# usbcan_20190426.net
KiCad netlist of a schematic drawn in EAGLE
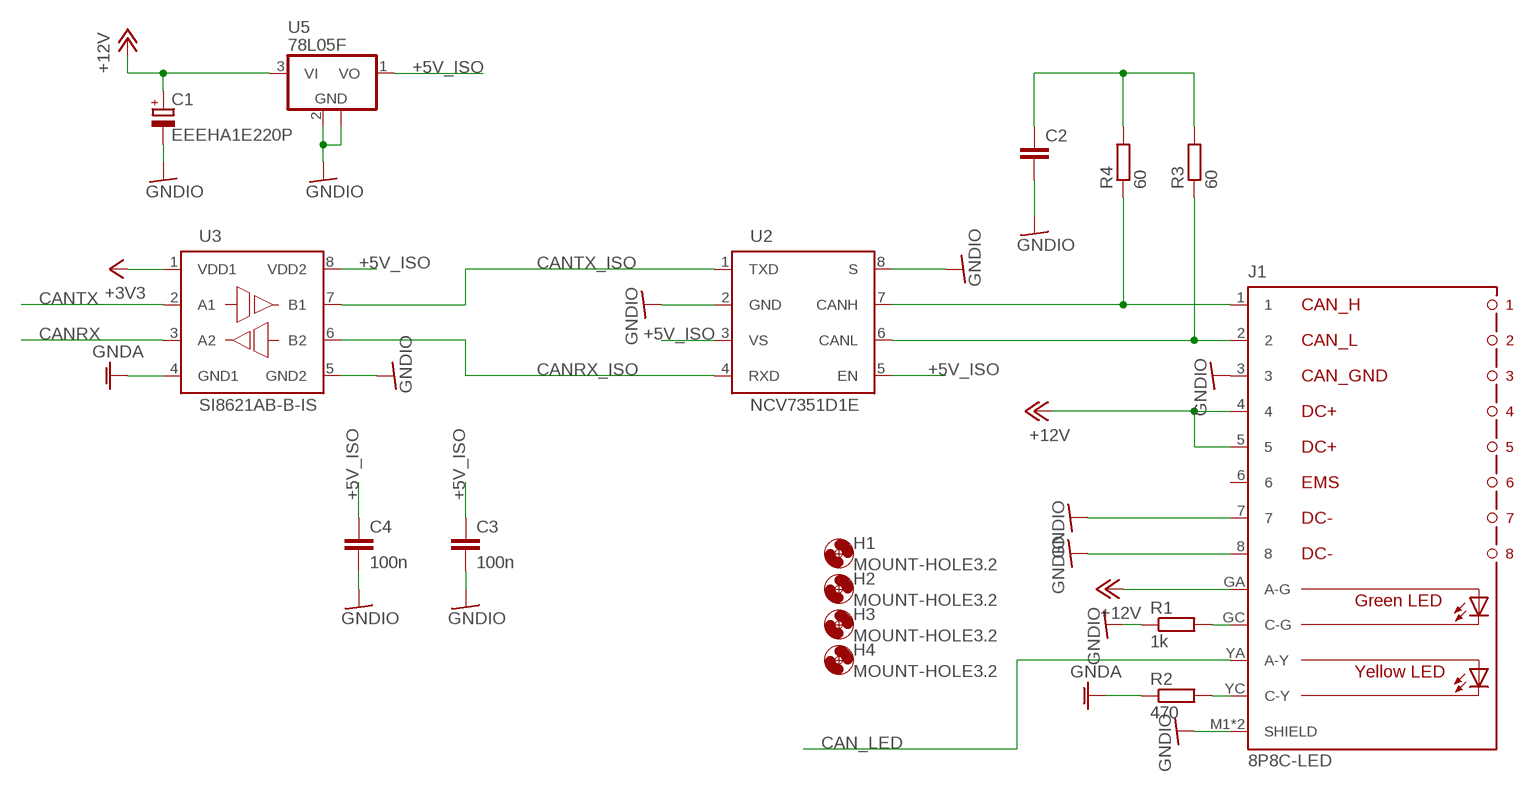
[diagram p0: schematic, sheet 1]
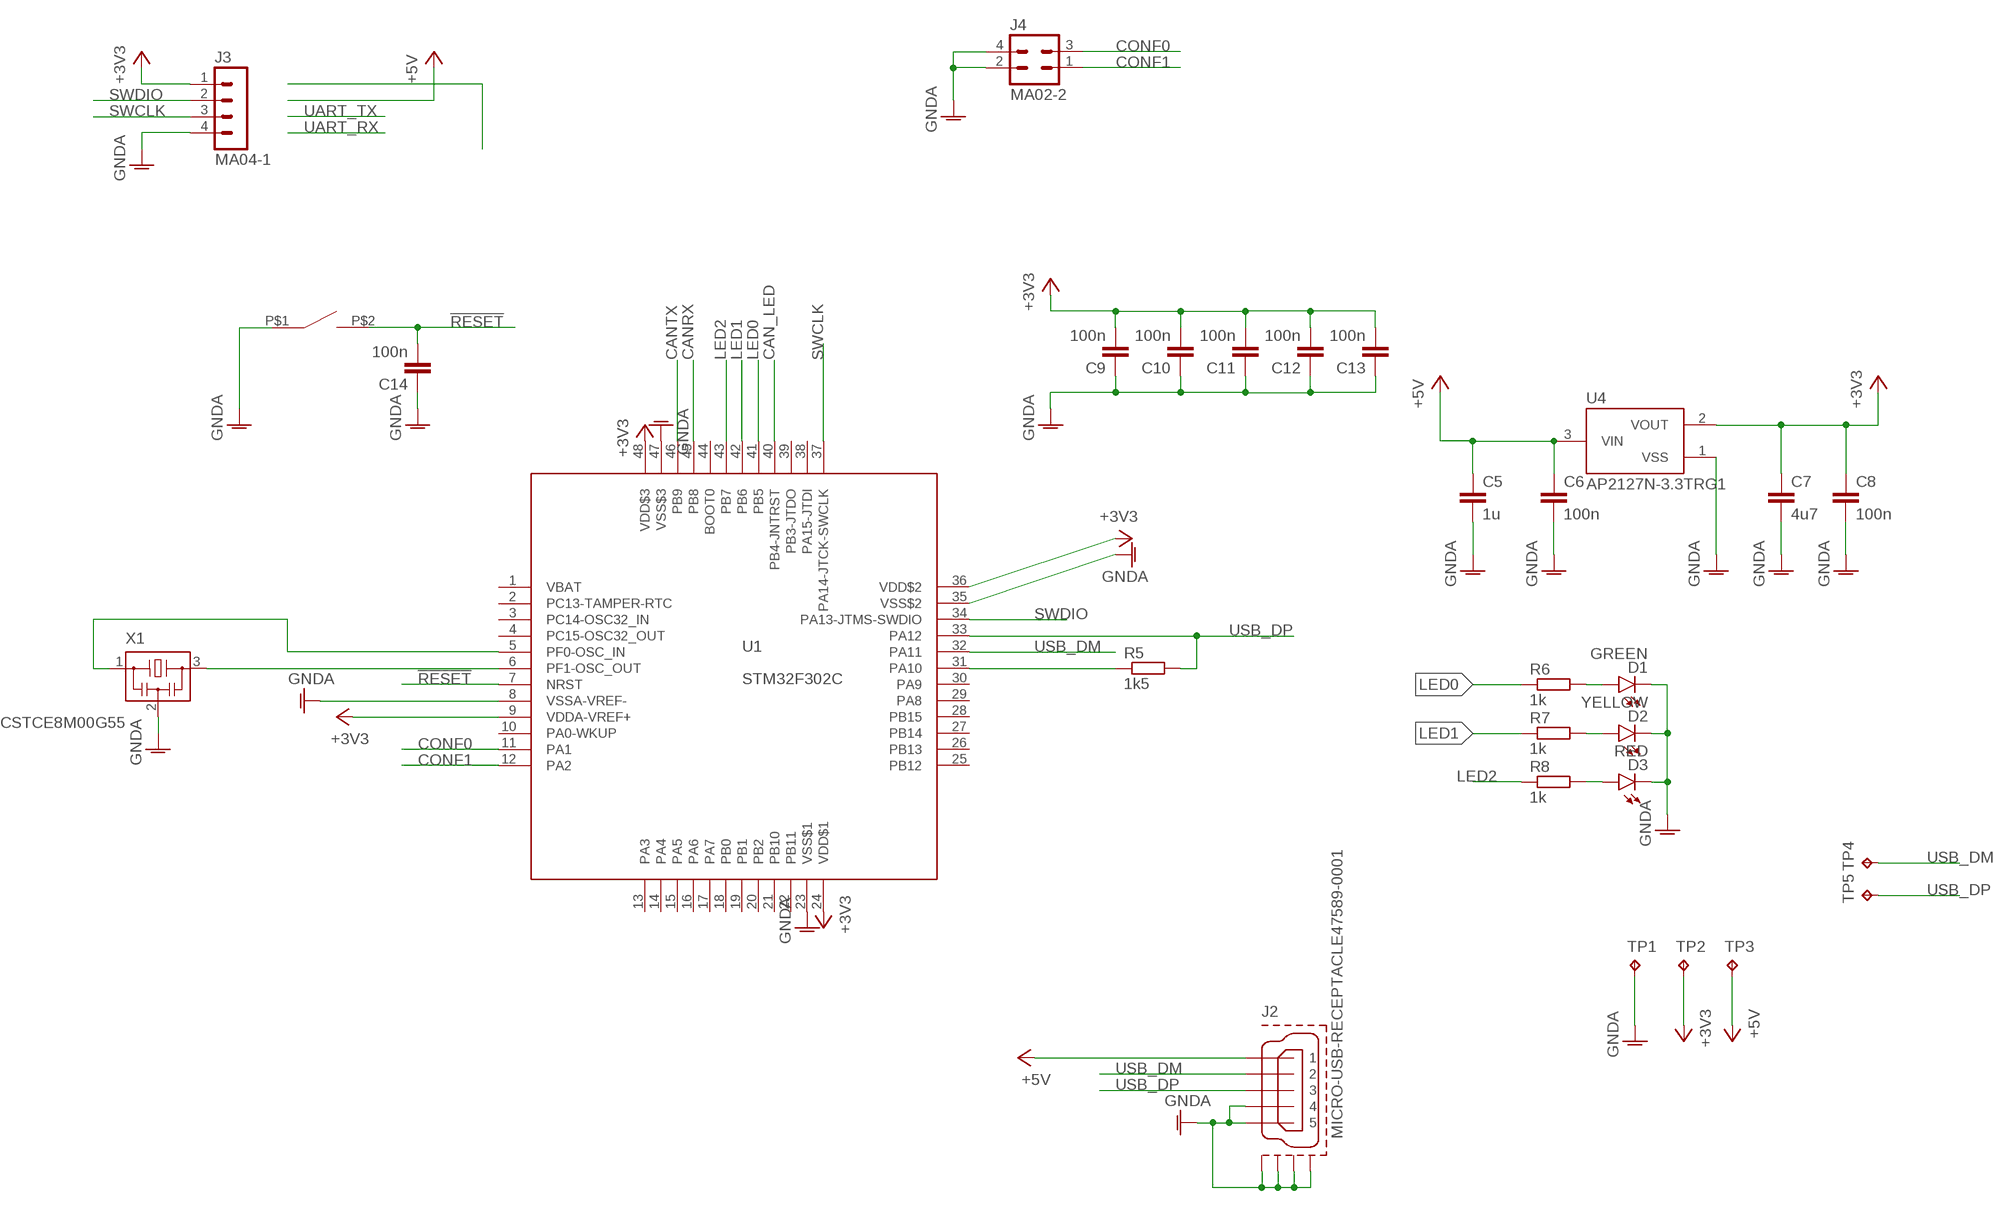
[diagram p1: schematic, sheet 2]

(export (version "E")
  (design (tool "Eeschema 10.0.6"))
  (components
    (comp (ref "C1")
      (value "EEEHA1E220P")
      (footprint "eagle-import:153CLV-0605")
      (libsource (lib "eagle-import") (part "CPOL-EU153CLV-0605"))
    )
    (comp (ref "C2")
      (value "C-EUC0603")
      (footprint "eagle-import:C0603")
      (libsource (lib "eagle-import") (part "rcl_334_C-EUC0603"))
    )
    (comp (ref "C3")
      (value "100n")
      (footprint "eagle-import:C0603")
      (libsource (lib "eagle-import") (part "rcl_334_C-EUC0603"))
    )
    (comp (ref "C4")
      (value "100n")
      (footprint "eagle-import:C0603")
      (libsource (lib "eagle-import") (part "rcl_334_C-EUC0603"))
    )
    (comp (ref "H1")
      (value "MOUNT-HOLE3.2")
      (footprint "eagle-import:3,2")
      (libsource (lib "eagle-import") (part "MOUNT-HOLE3.2"))
    )
    (comp (ref "H2")
      (value "MOUNT-HOLE3.2")
      (footprint "eagle-import:3,2")
      (libsource (lib "eagle-import") (part "MOUNT-HOLE3.2"))
    )
    (comp (ref "H3")
      (value "MOUNT-HOLE3.2")
      (footprint "eagle-import:3,2")
      (libsource (lib "eagle-import") (part "MOUNT-HOLE3.2"))
    )
    (comp (ref "H4")
      (value "MOUNT-HOLE3.2")
      (footprint "eagle-import:3,2")
      (libsource (lib "eagle-import") (part "MOUNT-HOLE3.2"))
    )
    (comp (ref "J1")
      (value "8P8C-LED")
      (footprint "eagle-import:8P8C-LED")
      (libsource (lib "eagle-import") (part "8P8C-LED"))
    )
    (comp (ref "R1")
      (value "1k")
      (footprint "eagle-import:R0603")
      (libsource (lib "eagle-import") (part "rcl_334_R-EU_R0603"))
    )
    (comp (ref "R2")
      (value "470")
      (footprint "eagle-import:R0603")
      (libsource (lib "eagle-import") (part "rcl_334_R-EU_R0603"))
    )
    (comp (ref "R3")
      (value "60")
      (footprint "eagle-import:R0603")
      (libsource (lib "eagle-import") (part "rcl_334_R-EU_R0603"))
    )
    (comp (ref "R4")
      (value "60")
      (footprint "eagle-import:R0603")
      (libsource (lib "eagle-import") (part "rcl_334_R-EU_R0603"))
    )
    (comp (ref "U2")
      (value "NCV7351D1E")
      (footprint "eagle-import:SO08")
      (libsource (lib "eagle-import") (part "NCV7351D1E"))
    )
    (comp (ref "U3")
      (value "SI8621AB-B-IS")
      (footprint "eagle-import:SO08")
      (libsource (lib "eagle-import") (part "SI8621AB-B-IS"))
    )
    (comp (ref "U5")
      (value "78L05F")
      (footprint "eagle-import:SOT89")
      (libsource (lib "eagle-import") (part "78LF05"))
    )
    (comp (ref "C5")
      (value "1u")
      (footprint "eagle-import:C0603")
      (libsource (lib "eagle-import") (part "C-EUC0603"))
    )
    (comp (ref "C6")
      (value "100n")
      (footprint "eagle-import:C0603")
      (libsource (lib "eagle-import") (part "C-EUC0603"))
    )
    (comp (ref "C7")
      (value "4u7")
      (footprint "eagle-import:C0805")
      (libsource (lib "eagle-import") (part "C-EUC0805"))
    )
    (comp (ref "C8")
      (value "100n")
      (footprint "eagle-import:C0603")
      (libsource (lib "eagle-import") (part "C-EUC0603"))
    )
    (comp (ref "C9")
      (value "100n")
      (footprint "eagle-import:C0603")
      (libsource (lib "eagle-import") (part "C-EUC0603"))
    )
    (comp (ref "C10")
      (value "100n")
      (footprint "eagle-import:C0603")
      (libsource (lib "eagle-import") (part "C-EUC0603"))
    )
    (comp (ref "C11")
      (value "100n")
      (footprint "eagle-import:C0603")
      (libsource (lib "eagle-import") (part "C-EUC0603"))
    )
    (comp (ref "C12")
      (value "100n")
      (footprint "eagle-import:C0603")
      (libsource (lib "eagle-import") (part "C-EUC0603"))
    )
    (comp (ref "C13")
      (value "100n")
      (footprint "eagle-import:C0603")
      (libsource (lib "eagle-import") (part "C-EUC0603"))
    )
    (comp (ref "C14")
      (value "100n")
      (footprint "eagle-import:C0603")
      (libsource (lib "eagle-import") (part "C-EUC0603"))
    )
    (comp (ref "D1")
      (value "GREEN")
      (footprint "eagle-import:CHIPLED_0805")
      (libsource (lib "eagle-import") (part "LEDCHIPLED_0805"))
    )
    (comp (ref "D2")
      (value "YELLOW")
      (footprint "eagle-import:CHIPLED_0805")
      (libsource (lib "eagle-import") (part "LEDCHIPLED_0805"))
    )
    (comp (ref "D3")
      (value "RED")
      (footprint "eagle-import:CHIPLED_0805")
      (libsource (lib "eagle-import") (part "LEDCHIPLED_0805"))
    )
    (comp (ref "J2")
      (value "MICRO-USB-RECEPTACLE47589-0001")
      (footprint "eagle-import:47589-0001")
      (libsource (lib "eagle-import") (part "MICRO-USB-RECEPTACLE47589-0001"))
    )
    (comp (ref "J3")
      (value "MA04-1")
      (footprint "eagle-import:MA04-1")
      (libsource (lib "eagle-import") (part "MA04-1"))
    )
    (comp (ref "J4")
      (value "MA02-2")
      (footprint "eagle-import:MA02-2W")
      (libsource (lib "eagle-import") (part "MA02-2"))
    )
    (comp (ref "R5")
      (value "1k5")
      (footprint "eagle-import:R0603")
      (libsource (lib "eagle-import") (part "R-EU_R0603"))
    )
    (comp (ref "R6")
      (value "1k")
      (footprint "eagle-import:R0603")
      (libsource (lib "eagle-import") (part "R-EU_R0603"))
    )
    (comp (ref "R7")
      (value "1k")
      (footprint "eagle-import:R0603")
      (libsource (lib "eagle-import") (part "R-EU_R0603"))
    )
    (comp (ref "R8")
      (value "1k")
      (footprint "eagle-import:R0603")
      (libsource (lib "eagle-import") (part "R-EU_R0603"))
    )
    (comp (ref "S1")
      (value "SWITCH_TACTILETOP")
      (footprint "eagle-import:SWITCH_TACTILE_3X6")
      (libsource (lib "eagle-import") (part "SWITCH_TACTILETOP"))
    )
    (comp (ref "TP1")
      (value "TPB1,27")
      (footprint "eagle-import:B1,27")
      (libsource (lib "eagle-import") (part "TPB1,27"))
    )
    (comp (ref "TP2")
      (value "TPB1,27")
      (footprint "eagle-import:B1,27")
      (libsource (lib "eagle-import") (part "TPB1,27"))
    )
    (comp (ref "TP3")
      (value "TPB1,27")
      (footprint "eagle-import:B1,27")
      (libsource (lib "eagle-import") (part "TPB1,27"))
    )
    (comp (ref "TP4")
      (value "TPB1,27")
      (footprint "eagle-import:B1,27")
      (libsource (lib "eagle-import") (part "TPB1,27"))
    )
    (comp (ref "TP5")
      (value "TPB1,27")
      (footprint "eagle-import:B1,27")
      (libsource (lib "eagle-import") (part "TPB1,27"))
    )
    (comp (ref "U1")
      (value "STM32F302C")
      (footprint "eagle-import:LQFP48")
      (libsource (lib "eagle-import") (part "STM32F303C"))
    )
    (comp (ref "U4")
      (value "AP2127N-3.3TRG1")
      (footprint "eagle-import:SOT95P240X110-3")
      (libsource (lib "eagle-import") (part "XC6206"))
    )
    (comp (ref "X1")
      (value "CSTCE8M00G55")
      (footprint "eagle-import:CSTCE8M00G55")
      (libsource (lib "eagle-import") (part "CSTCE8M00G55"))
    )
  )
  (nets
    (net (code "1") (name "+3V3") (class "Default")
      (node (ref "C10") (pin "2") (pinfunction "2_2") (pintype "passive"))
      (node (ref "C11") (pin "2") (pinfunction "2_2") (pintype "passive"))
      (node (ref "C12") (pin "2") (pinfunction "2_2") (pintype "passive"))
      (node (ref "C13") (pin "2") (pinfunction "2_2") (pintype "passive"))
      (node (ref "C7") (pin "1") (pinfunction "1_1") (pintype "passive"))
      (node (ref "C8") (pin "1") (pinfunction "1_1") (pintype "passive"))
      (node (ref "C9") (pin "2") (pinfunction "2_2") (pintype "passive"))
      (node (ref "J3") (pin "1") (pinfunction "1_1") (pintype "passive"))
      (node (ref "TP2") (pin "TP") (pinfunction "TP_TP") (pintype "input"))
      (node (ref "U1") (pin "24") (pinfunction "VDD$1_24") (pintype "passive"))
      (node (ref "U1") (pin "36") (pinfunction "VDD$2_36") (pintype "passive"))
      (node (ref "U1") (pin "48") (pinfunction "VDD$3_48") (pintype "passive"))
      (node (ref "U1") (pin "9") (pinfunction "VDDA-VREF+_9") (pintype "bidirectional"))
      (node (ref "U3") (pin "1") (pinfunction "VDD1_1") (pintype "power_in"))
      (node (ref "U4") (pin "2") (pinfunction "VOUT_2") (pintype "bidirectional"))
    )
    (net (code "2") (name "+5V") (class "Default")
      (node (ref "C5") (pin "1") (pinfunction "1_1") (pintype "passive"))
      (node (ref "C6") (pin "1") (pinfunction "1_1") (pintype "passive"))
      (node (ref "J2") (pin "1") (pinfunction "1_1") (pintype "input"))
      (node (ref "TP3") (pin "TP") (pinfunction "TP_TP") (pintype "input"))
      (node (ref "U4") (pin "3") (pinfunction "VIN_3") (pintype "bidirectional"))
    )
    (net (code "3") (name "+5V_ISO") (class "Default")
      (node (ref "C3") (pin "1") (pinfunction "1_1") (pintype "passive"))
      (node (ref "C4") (pin "1") (pinfunction "1_1") (pintype "passive"))
      (node (ref "U2") (pin "3") (pinfunction "VS_3") (pintype "power_in"))
      (node (ref "U2") (pin "5") (pinfunction "EN_5") (pintype "input"))
      (node (ref "U3") (pin "8") (pinfunction "VDD2_8") (pintype "power_in"))
      (node (ref "U5") (pin "1") (pinfunction "VO_1") (pintype "passive"))
    )
    (net (code "4") (name "+12V") (class "Default")
      (node (ref "C1") (pin "+") (pinfunction "+_+") (pintype "passive"))
      (node (ref "J1") (pin "4") (pinfunction "4_4") (pintype "input"))
      (node (ref "J1") (pin "5") (pinfunction "5_5") (pintype "input"))
      (node (ref "J1") (pin "GA") (pinfunction "A-G_GA") (pintype "passive"))
      (node (ref "U5") (pin "3") (pinfunction "VI_3") (pintype "input"))
    )
    (net (code "5") (name "CANRX") (class "Default")
      (node (ref "U1") (pin "45") (pinfunction "PB8_45") (pintype "bidirectional"))
      (node (ref "U3") (pin "3") (pinfunction "A2_3") (pintype "output"))
    )
    (net (code "6") (name "CANRX_ISO") (class "Default")
      (node (ref "U2") (pin "4") (pinfunction "RXD_4") (pintype "output"))
      (node (ref "U3") (pin "6") (pinfunction "B2_6") (pintype "output"))
    )
    (net (code "7") (name "CANTX") (class "Default")
      (node (ref "U1") (pin "46") (pinfunction "PB9_46") (pintype "bidirectional"))
      (node (ref "U3") (pin "2") (pinfunction "A1_2") (pintype "input"))
    )
    (net (code "8") (name "CANTX_ISO") (class "Default")
      (node (ref "U2") (pin "1") (pinfunction "TXD_1") (pintype "input"))
      (node (ref "U3") (pin "7") (pinfunction "B1_7") (pintype "output"))
    )
    (net (code "9") (name "CAN_LED") (class "Default")
      (node (ref "J1") (pin "YA") (pinfunction "A-Y_YA") (pintype "passive"))
      (node (ref "U1") (pin "40") (pinfunction "PB4-JNTRST_40") (pintype "bidirectional"))
    )
    (net (code "10") (name "CONF0") (class "Default")
      (node (ref "J4") (pin "3") (pinfunction "3_3") (pintype "passive"))
      (node (ref "U1") (pin "11") (pinfunction "PA1_11") (pintype "bidirectional"))
    )
    (net (code "11") (name "CONF1") (class "Default")
      (node (ref "J4") (pin "1") (pinfunction "1_1") (pintype "passive"))
      (node (ref "U1") (pin "12") (pinfunction "PA2_12") (pintype "bidirectional"))
    )
    (net (code "12") (name "GNDA") (class "Default")
      (node (ref "C10") (pin "1") (pinfunction "1_1") (pintype "passive"))
      (node (ref "C11") (pin "1") (pinfunction "1_1") (pintype "passive"))
      (node (ref "C12") (pin "1") (pinfunction "1_1") (pintype "passive"))
      (node (ref "C13") (pin "1") (pinfunction "1_1") (pintype "passive"))
      (node (ref "C14") (pin "1") (pinfunction "1_1") (pintype "passive"))
      (node (ref "C5") (pin "2") (pinfunction "2_2") (pintype "passive"))
      (node (ref "C6") (pin "2") (pinfunction "2_2") (pintype "passive"))
      (node (ref "C7") (pin "2") (pinfunction "2_2") (pintype "passive"))
      (node (ref "C8") (pin "2") (pinfunction "2_2") (pintype "passive"))
      (node (ref "C9") (pin "1") (pinfunction "1_1") (pintype "passive"))
      (node (ref "D1") (pin "C") (pinfunction "C_C") (pintype "passive"))
      (node (ref "D2") (pin "C") (pinfunction "C_C") (pintype "passive"))
      (node (ref "D3") (pin "C") (pinfunction "C_C") (pintype "passive"))
      (node (ref "J2") (pin "4") (pinfunction "4_4") (pintype "input"))
      (node (ref "J2") (pin "5") (pinfunction "5_5") (pintype "input"))
      (node (ref "J2") (pin "CASING1") (pinfunction "GND1_CASING1") (pintype "bidirectional"))
      (node (ref "J2") (pin "CASING2") (pinfunction "GND2_CASING2") (pintype "bidirectional"))
      (node (ref "J2") (pin "CASING3") (pinfunction "GND3_CASING3") (pintype "bidirectional"))
      (node (ref "J2") (pin "CASING4") (pinfunction "GND4_CASING4") (pintype "bidirectional"))
      (node (ref "J2") (pin "P$1") (pinfunction "GND1_P$1") (pintype "bidirectional"))
      (node (ref "J2") (pin "P$2") (pinfunction "GND1_P$2") (pintype "bidirectional"))
      (node (ref "J2") (pin "P$3") (pinfunction "GND2_P$3") (pintype "bidirectional"))
      (node (ref "J2") (pin "P$4") (pinfunction "GND2_P$4") (pintype "bidirectional"))
      (node (ref "J3") (pin "4") (pinfunction "4_4") (pintype "passive"))
      (node (ref "J4") (pin "2") (pinfunction "2_2") (pintype "passive"))
      (node (ref "J4") (pin "4") (pinfunction "4_4") (pintype "passive"))
      (node (ref "R2") (pin "1") (pinfunction "1_1") (pintype "passive"))
      (node (ref "S1") (pin "P$1") (pinfunction "1_P$1") (pintype "bidirectional"))
      (node (ref "TP1") (pin "TP") (pinfunction "TP_TP") (pintype "input"))
      (node (ref "U1") (pin "23") (pinfunction "VSS$1_23") (pintype "passive"))
      (node (ref "U1") (pin "35") (pinfunction "VSS$2_35") (pintype "passive"))
      (node (ref "U1") (pin "47") (pinfunction "VSS$3_47") (pintype "passive"))
      (node (ref "U1") (pin "8") (pinfunction "VSSA-VREF-_8") (pintype "bidirectional"))
      (node (ref "U3") (pin "4") (pinfunction "GND1_4") (pintype "power_in"))
      (node (ref "U4") (pin "1") (pinfunction "VSS_1") (pintype "bidirectional"))
      (node (ref "X1") (pin "2") (pinfunction "2_2") (pintype "passive"))
    )
    (net (code "13") (name "GNDIO") (class "Default")
      (node (ref "C1") (pin "-") (pinfunction "-_-") (pintype "passive"))
      (node (ref "C2") (pin "2") (pinfunction "2_2") (pintype "passive"))
      (node (ref "C3") (pin "2") (pinfunction "2_2") (pintype "passive"))
      (node (ref "C4") (pin "2") (pinfunction "2_2") (pintype "passive"))
      (node (ref "J1") (pin "3") (pinfunction "3_3") (pintype "input"))
      (node (ref "J1") (pin "7") (pinfunction "7_7") (pintype "input"))
      (node (ref "J1") (pin "8") (pinfunction "8_8") (pintype "input"))
      (node (ref "J1") (pin "M1") (pinfunction "SHIELD_M1") (pintype "passive"))
      (node (ref "J1") (pin "M2") (pinfunction "SHIELD_M2") (pintype "passive"))
      (node (ref "R1") (pin "1") (pinfunction "1_1") (pintype "passive"))
      (node (ref "U2") (pin "2") (pinfunction "GND_2") (pintype "power_in"))
      (node (ref "U2") (pin "8") (pinfunction "S_8") (pintype "input"))
      (node (ref "U3") (pin "5") (pinfunction "GND2_5") (pintype "power_in"))
      (node (ref "U5") (pin "2") (pinfunction "GND_2") (pintype "passive"))
      (node (ref "U5") (pin "2@1") (pinfunction "GND_2@1") (pintype "passive"))
    )
    (net (code "14") (name "LED0") (class "Default")
      (node (ref "R6") (pin "1") (pinfunction "1_1") (pintype "passive"))
      (node (ref "U1") (pin "41") (pinfunction "PB5_41") (pintype "bidirectional"))
    )
    (net (code "15") (name "LED1") (class "Default")
      (node (ref "R7") (pin "1") (pinfunction "1_1") (pintype "passive"))
      (node (ref "U1") (pin "42") (pinfunction "PB6_42") (pintype "bidirectional"))
    )
    (net (code "16") (name "LED2") (class "Default")
      (node (ref "R8") (pin "1") (pinfunction "1_1") (pintype "passive"))
      (node (ref "U1") (pin "43") (pinfunction "PB7_43") (pintype "bidirectional"))
    )
    (net (code "17") (name "Net-(C2-Pad1)") (class "Default")
      (node (ref "C2") (pin "1") (pinfunction "1_1") (pintype "passive"))
      (node (ref "R3") (pin "2") (pinfunction "2_2") (pintype "passive"))
      (node (ref "R4") (pin "2") (pinfunction "2_2") (pintype "passive"))
    )
    (net (code "18") (name "Net-(D1-PadA)") (class "Default")
      (node (ref "D1") (pin "A") (pinfunction "A_A") (pintype "passive"))
      (node (ref "R6") (pin "2") (pinfunction "2_2") (pintype "passive"))
    )
    (net (code "19") (name "Net-(D2-PadA)") (class "Default")
      (node (ref "D2") (pin "A") (pinfunction "A_A") (pintype "passive"))
      (node (ref "R7") (pin "2") (pinfunction "2_2") (pintype "passive"))
    )
    (net (code "20") (name "Net-(D3-PadA)") (class "Default")
      (node (ref "D3") (pin "A") (pinfunction "A_A") (pintype "passive"))
      (node (ref "R8") (pin "2") (pinfunction "2_2") (pintype "passive"))
    )
    (net (code "21") (name "Net-(J1-C-G)") (class "Default")
      (node (ref "J1") (pin "GC") (pinfunction "C-G_GC") (pintype "passive"))
      (node (ref "R1") (pin "2") (pinfunction "2_2") (pintype "passive"))
    )
    (net (code "22") (name "Net-(J1-C-Y)") (class "Default")
      (node (ref "J1") (pin "YC") (pinfunction "C-Y_YC") (pintype "passive"))
      (node (ref "R2") (pin "2") (pinfunction "2_2") (pintype "passive"))
    )
    (net (code "23") (name "Net-(U1-PA10)") (class "Default")
      (node (ref "R5") (pin "1") (pinfunction "1_1") (pintype "passive"))
      (node (ref "U1") (pin "31") (pinfunction "PA10_31") (pintype "bidirectional"))
    )
    (net (code "24") (name "Net-(U1-PF0-OSC_IN)") (class "Default")
      (node (ref "U1") (pin "5") (pinfunction "PF0-OSC_IN_5") (pintype "input"))
      (node (ref "X1") (pin "1") (pinfunction "1_1") (pintype "passive"))
    )
    (net (code "25") (name "Net-(U1-PF1-OSC_OUT)") (class "Default")
      (node (ref "U1") (pin "6") (pinfunction "PF1-OSC_OUT_6") (pintype "output"))
      (node (ref "X1") (pin "3") (pinfunction "3_3") (pintype "passive"))
    )
    (net (code "26") (name "Net-(U2-CANH)") (class "Default")
      (node (ref "J1") (pin "1") (pinfunction "1_1") (pintype "input"))
      (node (ref "R4") (pin "1") (pinfunction "1_1") (pintype "passive"))
      (node (ref "U2") (pin "7") (pinfunction "CANH_7") (pintype "output"))
    )
    (net (code "27") (name "Net-(U2-CANL)") (class "Default")
      (node (ref "J1") (pin "2") (pinfunction "2_2") (pintype "input"))
      (node (ref "R3") (pin "1") (pinfunction "1_1") (pintype "passive"))
      (node (ref "U2") (pin "6") (pinfunction "CANL_6") (pintype "output"))
    )
    (net (code "28") (name "SWCLK") (class "Default")
      (node (ref "J3") (pin "3") (pinfunction "3_3") (pintype "passive"))
      (node (ref "U1") (pin "37") (pinfunction "PA14-JTCK-SWCLK_37") (pintype "bidirectional"))
    )
    (net (code "29") (name "SWDIO") (class "Default")
      (node (ref "J3") (pin "2") (pinfunction "2_2") (pintype "passive"))
      (node (ref "U1") (pin "34") (pinfunction "PA13-JTMS-SWDIO_34") (pintype "bidirectional"))
    )
    (net (code "32") (name "USB_DM") (class "Default")
      (node (ref "J2") (pin "2") (pinfunction "2_2") (pintype "input"))
      (node (ref "TP4") (pin "TP") (pinfunction "TP_TP") (pintype "input"))
      (node (ref "U1") (pin "32") (pinfunction "PA11_32") (pintype "bidirectional"))
    )
    (net (code "33") (name "USB_DP") (class "Default")
      (node (ref "J2") (pin "3") (pinfunction "3_3") (pintype "input"))
      (node (ref "R5") (pin "2") (pinfunction "2_2") (pintype "passive"))
      (node (ref "TP5") (pin "TP") (pinfunction "TP_TP") (pintype "input"))
      (node (ref "U1") (pin "33") (pinfunction "PA12_33") (pintype "bidirectional"))
    )
    (net (code "34") (name "unconnected-(J1-Pad6)") (class "Default")
      (node (ref "J1") (pin "6") (pinfunction "6_6") (pintype "input"))
    )
    (net (code "35") (name "unconnected-(U1-BOOT0-Pad44)") (class "Default")
      (node (ref "U1") (pin "44") (pinfunction "BOOT0_44") (pintype "input"))
    )
    (net (code "36") (name "unconnected-(U1-PA0-WKUP-Pad10)") (class "Default")
      (node (ref "U1") (pin "10") (pinfunction "PA0-WKUP_10") (pintype "bidirectional"))
    )
    (net (code "37") (name "unconnected-(U1-PA3-Pad13)") (class "Default")
      (node (ref "U1") (pin "13") (pinfunction "PA3_13") (pintype "bidirectional"))
    )
    (net (code "38") (name "unconnected-(U1-PA4-Pad14)") (class "Default")
      (node (ref "U1") (pin "14") (pinfunction "PA4_14") (pintype "bidirectional"))
    )
    (net (code "39") (name "unconnected-(U1-PA5-Pad15)") (class "Default")
      (node (ref "U1") (pin "15") (pinfunction "PA5_15") (pintype "bidirectional"))
    )
    (net (code "40") (name "unconnected-(U1-PA6-Pad16)") (class "Default")
      (node (ref "U1") (pin "16") (pinfunction "PA6_16") (pintype "bidirectional"))
    )
    (net (code "41") (name "unconnected-(U1-PA7-Pad17)") (class "Default")
      (node (ref "U1") (pin "17") (pinfunction "PA7_17") (pintype "bidirectional"))
    )
    (net (code "42") (name "unconnected-(U1-PA8-Pad29)") (class "Default")
      (node (ref "U1") (pin "29") (pinfunction "PA8_29") (pintype "bidirectional"))
    )
    (net (code "43") (name "unconnected-(U1-PA9-Pad30)") (class "Default")
      (node (ref "U1") (pin "30") (pinfunction "PA9_30") (pintype "bidirectional"))
    )
    (net (code "44") (name "unconnected-(U1-PA15-JTDI-Pad38)") (class "Default")
      (node (ref "U1") (pin "38") (pinfunction "PA15-JTDI_38") (pintype "bidirectional"))
    )
    (net (code "45") (name "unconnected-(U1-PB0-Pad18)") (class "Default")
      (node (ref "U1") (pin "18") (pinfunction "PB0_18") (pintype "bidirectional"))
    )
    (net (code "46") (name "unconnected-(U1-PB1-Pad19)") (class "Default")
      (node (ref "U1") (pin "19") (pinfunction "PB1_19") (pintype "bidirectional"))
    )
    (net (code "47") (name "unconnected-(U1-PB2-Pad20)") (class "Default")
      (node (ref "U1") (pin "20") (pinfunction "PB2_20") (pintype "bidirectional"))
    )
    (net (code "48") (name "unconnected-(U1-PB3-JTDO-Pad39)") (class "Default")
      (node (ref "U1") (pin "39") (pinfunction "PB3-JTDO_39") (pintype "bidirectional"))
    )
    (net (code "49") (name "unconnected-(U1-PB10-Pad21)") (class "Default")
      (node (ref "U1") (pin "21") (pinfunction "PB10_21") (pintype "bidirectional"))
    )
    (net (code "50") (name "unconnected-(U1-PB11-Pad22)") (class "Default")
      (node (ref "U1") (pin "22") (pinfunction "PB11_22") (pintype "bidirectional"))
    )
    (net (code "51") (name "unconnected-(U1-PB12-Pad25)") (class "Default")
      (node (ref "U1") (pin "25") (pinfunction "PB12_25") (pintype "bidirectional"))
    )
    (net (code "52") (name "unconnected-(U1-PB13-Pad26)") (class "Default")
      (node (ref "U1") (pin "26") (pinfunction "PB13_26") (pintype "bidirectional"))
    )
    (net (code "53") (name "unconnected-(U1-PB14-Pad27)") (class "Default")
      (node (ref "U1") (pin "27") (pinfunction "PB14_27") (pintype "bidirectional"))
    )
    (net (code "54") (name "unconnected-(U1-PB15-Pad28)") (class "Default")
      (node (ref "U1") (pin "28") (pinfunction "PB15_28") (pintype "bidirectional"))
    )
    (net (code "55") (name "unconnected-(U1-PC13-TAMPER-RTC-Pad2)") (class "Default")
      (node (ref "U1") (pin "2") (pinfunction "PC13-TAMPER-RTC_2") (pintype "bidirectional"))
    )
    (net (code "56") (name "unconnected-(U1-PC14-OSC32_IN-Pad3)") (class "Default")
      (node (ref "U1") (pin "3") (pinfunction "PC14-OSC32_IN_3") (pintype "bidirectional"))
    )
    (net (code "57") (name "unconnected-(U1-PC15-OSC32_OUT-Pad4)") (class "Default")
      (node (ref "U1") (pin "4") (pinfunction "PC15-OSC32_OUT_4") (pintype "bidirectional"))
    )
    (net (code "58") (name "unconnected-(U1-VBAT-Pad1)") (class "Default")
      (node (ref "U1") (pin "1") (pinfunction "VBAT_1") (pintype "passive"))
    )
    (net (code "59") (name "~{RESET}") (class "Default")
      (node (ref "C14") (pin "2") (pinfunction "2_2") (pintype "passive"))
      (node (ref "S1") (pin "P$2") (pinfunction "2_P$2") (pintype "bidirectional"))
      (node (ref "U1") (pin "7") (pinfunction "NRST_7") (pintype "bidirectional"))
    )
  )
)
